# RC_LPF_PI.net
KiCad netlist of a schematic drawn in Altium Designer
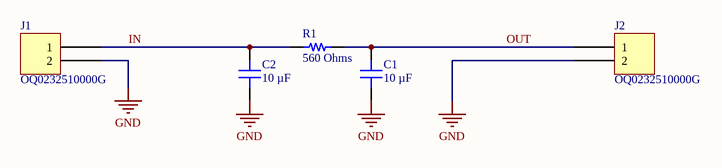
[diagram p0: RC_LPF_PI.SchDoc]

(export (version "E")
  (design (tool "Eeschema 10.0.6"))
  (components
    (comp (ref "C1")
      (value "10 µF")
      (footprint "CAP 0603_1608")
      (description "CAP CER 10UF 10V X5R 0603")
      (fields
        (field (name "PART NUMBER") "MD0603BW106M100NHT-EM")
        (field (name "MANUFACTURER") "Knowles Novacap")
      )
      (libsource (lib "Celestial Altium Library - altium_library") (part "Capacitor"))
    )
    (comp (ref "C2")
      (value "10 µF")
      (footprint "CAP 0603_1608")
      (description "CAP CER 10UF 10V X5R 0603")
      (fields
        (field (name "PART NUMBER") "MD0603BW106M100NHT-EM")
        (field (name "MANUFACTURER") "Knowles Novacap")
      )
      (libsource (lib "Celestial Altium Library - altium_library") (part "Capacitor"))
    )
    (comp (ref "J1")
      (value "OQ0232510000G")
      (footprint "FCI 06-381-2PIN")
      (description "TERM BLOCK HDR 2POS 90DEG 3.81MM")
      (fields (field (name "MANUFACTURER") "Amphenol Anytek"))
      (libsource (lib "Celestial Altium Library - altium_library") (part "2 Pin"))
    )
    (comp (ref "J2")
      (value "OQ0232510000G")
      (footprint "FCI 06-381-2PIN")
      (description "TERM BLOCK HDR 2POS 90DEG 3.81MM")
      (fields (field (name "MANUFACTURER") "Amphenol Anytek"))
      (libsource (lib "") (part "2 Pin_1"))
    )
    (comp (ref "R1")
      (value "560 Ohms")
      (footprint "RES 0603_1608")
      (description "RES 560 OHM 1% 1/4W 0603")
      (fields
        (field (name "PART NUMBER") "CRGP0603F560R")
        (field (name "MANUFACTURER") "TE Connectivity Passive Product")
      )
      (libsource (lib "Celestial Altium Library - altium_library") (part "Resistor"))
    )
  )
  (nets
    (net (code "1") (name "/IN") (class "Default")
      (node (ref "C2") (pin "2") (pinfunction "2_2") (pintype "passive"))
      (node (ref "J1") (pin "1") (pinfunction "1_1") (pintype "passive"))
      (node (ref "R1") (pin "1") (pinfunction "1_1") (pintype "passive"))
    )
    (net (code "2") (name "/OUT") (class "Default")
      (node (ref "C1") (pin "2") (pinfunction "2_2") (pintype "passive"))
      (node (ref "J2") (pin "1") (pinfunction "1_1") (pintype "passive"))
      (node (ref "R1") (pin "2") (pinfunction "2_2") (pintype "passive"))
    )
    (net (code "3") (name "GND") (class "Default")
      (node (ref "C1") (pin "1") (pinfunction "1_1") (pintype "passive"))
      (node (ref "C2") (pin "1") (pinfunction "1_1") (pintype "passive"))
      (node (ref "J1") (pin "2") (pinfunction "2_2") (pintype "passive"))
      (node (ref "J2") (pin "2") (pinfunction "2_2") (pintype "passive"))
    )
  )
)
